# 5x4-soundboard_328p_TQFP.net
KiCad netlist of a schematic drawn in EAGLE
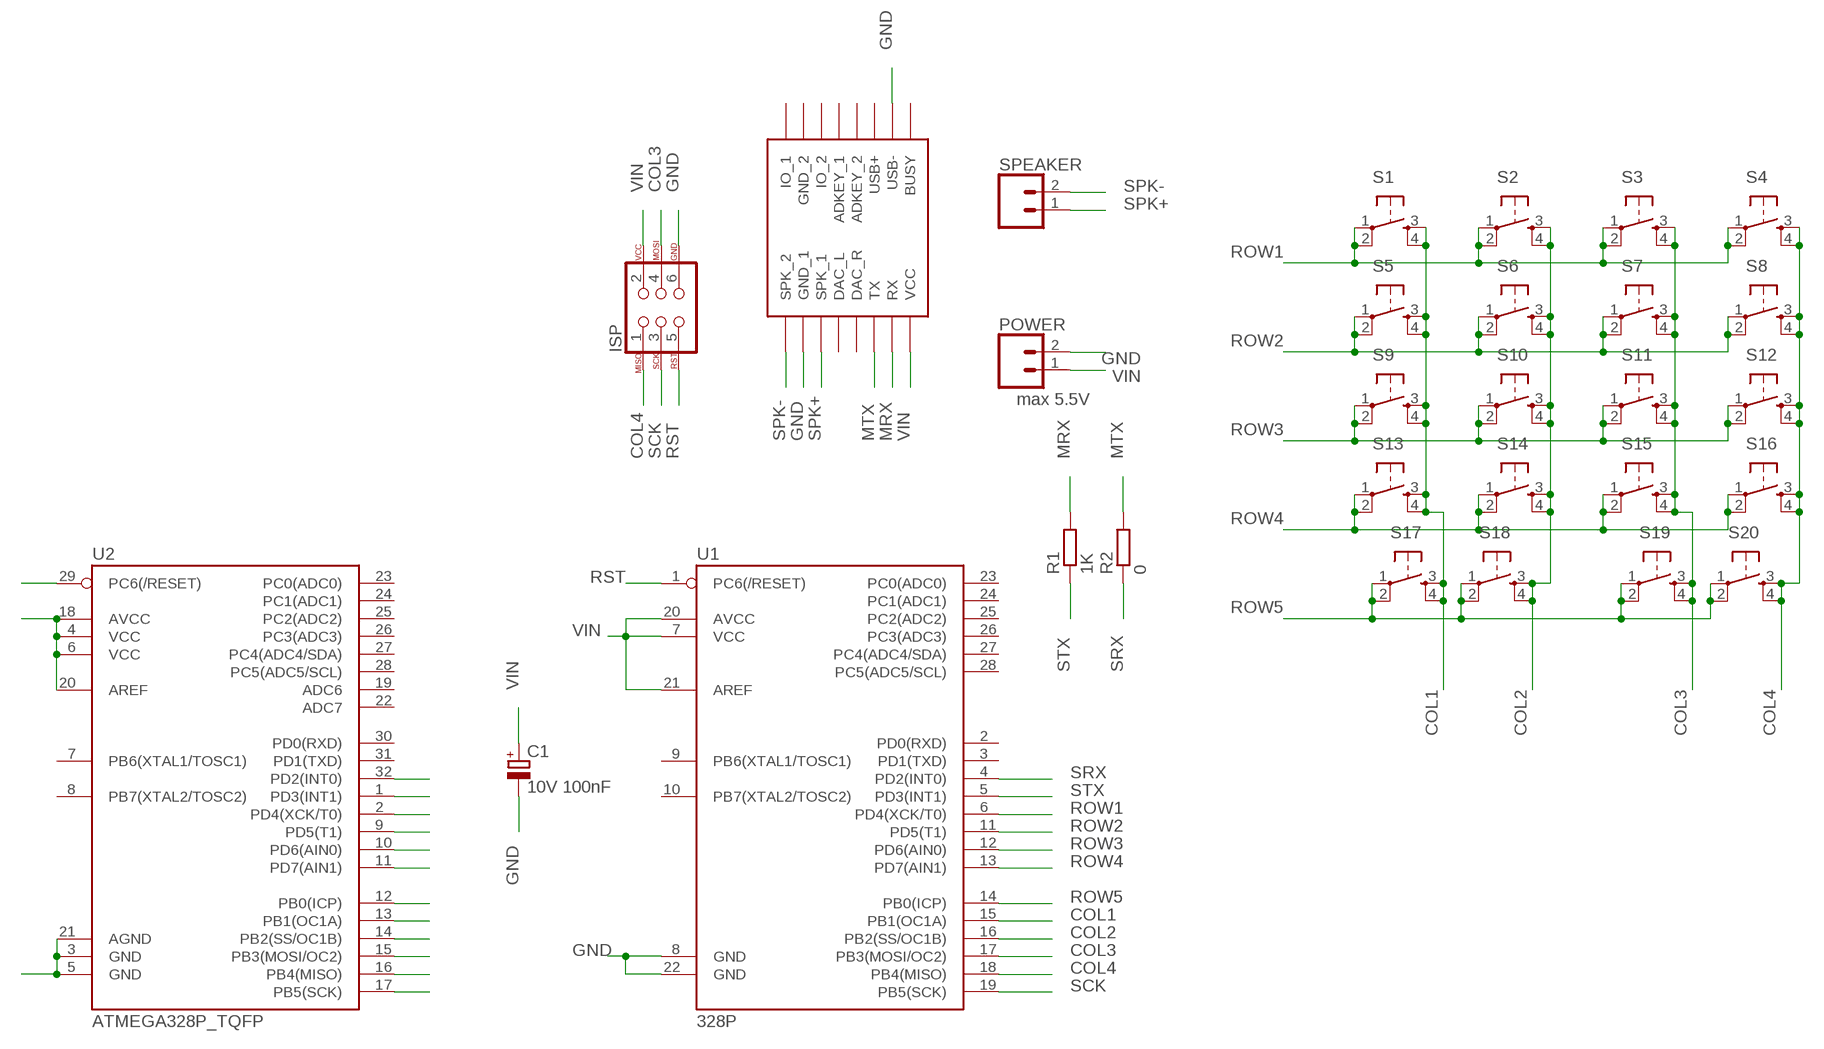
[diagram p0: schematic, sheet 1]

(export (version "E")
  (design (tool "Eeschema 10.0.6"))
  (components
    (comp (ref "C1")
      (value "10V 100nF")
      (footprint "eagle-import:E5-6")
      (libsource (lib "eagle-import") (part "CPOL-EUE5-6"))
    )
    (comp (ref "ISP")
      (value "AVR_SPI_PROG_3X2PTH")
      (footprint "eagle-import:2X3")
      (libsource (lib "eagle-import") (part "AVR_SPI_PROG_3X2PTH"))
    )
    (comp (ref "POWER")
      (value "CONN_02LOCK_LONGPADS")
      (footprint "eagle-import:1X02_LOCK_LONGPADS")
      (libsource (lib "eagle-import") (part "CONN_02LOCK_LONGPADS"))
    )
    (comp (ref "R1")
      (value "1K")
      (footprint "eagle-import:0207_10")
      (libsource (lib "eagle-import") (part "R-EU_0207/10"))
    )
    (comp (ref "R2")
      (value "0")
      (footprint "eagle-import:0207_10")
      (libsource (lib "eagle-import") (part "R-EU_0207/10"))
    )
    (comp (ref "S1")
      (value "TAC_SWITCHPTH")
      (footprint "eagle-import:TACTILE-PTH")
      (libsource (lib "eagle-import") (part "TAC_SWITCHPTH"))
    )
    (comp (ref "S2")
      (value "TAC_SWITCHPTH")
      (footprint "eagle-import:TACTILE-PTH")
      (libsource (lib "eagle-import") (part "TAC_SWITCHPTH"))
    )
    (comp (ref "S3")
      (value "TAC_SWITCHPTH")
      (footprint "eagle-import:TACTILE-PTH")
      (libsource (lib "eagle-import") (part "TAC_SWITCHPTH"))
    )
    (comp (ref "S4")
      (value "TAC_SWITCHPTH")
      (footprint "eagle-import:TACTILE-PTH")
      (libsource (lib "eagle-import") (part "TAC_SWITCHPTH"))
    )
    (comp (ref "S5")
      (value "TAC_SWITCHPTH")
      (footprint "eagle-import:TACTILE-PTH")
      (libsource (lib "eagle-import") (part "TAC_SWITCHPTH"))
    )
    (comp (ref "S6")
      (value "TAC_SWITCHPTH")
      (footprint "eagle-import:TACTILE-PTH")
      (libsource (lib "eagle-import") (part "TAC_SWITCHPTH"))
    )
    (comp (ref "S7")
      (value "TAC_SWITCHPTH")
      (footprint "eagle-import:TACTILE-PTH")
      (libsource (lib "eagle-import") (part "TAC_SWITCHPTH"))
    )
    (comp (ref "S8")
      (value "TAC_SWITCHPTH")
      (footprint "eagle-import:TACTILE-PTH")
      (libsource (lib "eagle-import") (part "TAC_SWITCHPTH"))
    )
    (comp (ref "S9")
      (value "TAC_SWITCHPTH")
      (footprint "eagle-import:TACTILE-PTH")
      (libsource (lib "eagle-import") (part "TAC_SWITCHPTH"))
    )
    (comp (ref "S10")
      (value "TAC_SWITCHPTH")
      (footprint "eagle-import:TACTILE-PTH")
      (libsource (lib "eagle-import") (part "TAC_SWITCHPTH"))
    )
    (comp (ref "S11")
      (value "TAC_SWITCHPTH")
      (footprint "eagle-import:TACTILE-PTH")
      (libsource (lib "eagle-import") (part "TAC_SWITCHPTH"))
    )
    (comp (ref "S12")
      (value "TAC_SWITCHPTH")
      (footprint "eagle-import:TACTILE-PTH")
      (libsource (lib "eagle-import") (part "TAC_SWITCHPTH"))
    )
    (comp (ref "S13")
      (value "TAC_SWITCHPTH")
      (footprint "eagle-import:TACTILE-PTH")
      (libsource (lib "eagle-import") (part "TAC_SWITCHPTH"))
    )
    (comp (ref "S14")
      (value "TAC_SWITCHPTH")
      (footprint "eagle-import:TACTILE-PTH")
      (libsource (lib "eagle-import") (part "TAC_SWITCHPTH"))
    )
    (comp (ref "S15")
      (value "TAC_SWITCHPTH")
      (footprint "eagle-import:TACTILE-PTH")
      (libsource (lib "eagle-import") (part "TAC_SWITCHPTH"))
    )
    (comp (ref "S16")
      (value "TAC_SWITCHPTH")
      (footprint "eagle-import:TACTILE-PTH")
      (libsource (lib "eagle-import") (part "TAC_SWITCHPTH"))
    )
    (comp (ref "S17")
      (value "TAC_SWITCHPTH")
      (footprint "eagle-import:TACTILE-PTH")
      (libsource (lib "eagle-import") (part "TAC_SWITCHPTH"))
    )
    (comp (ref "S18")
      (value "TAC_SWITCHPTH")
      (footprint "eagle-import:TACTILE-PTH")
      (libsource (lib "eagle-import") (part "TAC_SWITCHPTH"))
    )
    (comp (ref "S19")
      (value "TAC_SWITCHPTH")
      (footprint "eagle-import:TACTILE-PTH")
      (libsource (lib "eagle-import") (part "TAC_SWITCHPTH"))
    )
    (comp (ref "S20")
      (value "TAC_SWITCHPTH")
      (footprint "eagle-import:TACTILE-PTH")
      (libsource (lib "eagle-import") (part "TAC_SWITCHPTH"))
    )
    (comp (ref "SPEAKER")
      (value "CONN_02LOCK_LONGPADS")
      (footprint "eagle-import:1X02_LOCK_LONGPADS")
      (libsource (lib "eagle-import") (part "CONN_02LOCK_LONGPADS"))
    )
    (comp (ref "U$1")
      (value "DFPLAYER")
      (footprint "eagle-import:DFPLAYER")
      (libsource (lib "eagle-import") (part "DFPLAYER"))
    )
    (comp (ref "U1")
      (value "328P")
      (footprint "eagle-import:DIP28")
      (libsource (lib "eagle-import") (part "ATMEGA328P_PDIP"))
    )
    (comp (ref "U2")
      (value "ATMEGA328P_TQFP")
      (footprint "eagle-import:TQFP32-08")
      (libsource (lib "eagle-import") (part "ATMEGA328P_TQFP"))
    )
  )
  (nets
    (net (code "1") (name "/COL1") (class "Default")
      (node (ref "S1") (pin "3") (pinfunction "3_3") (pintype "passive"))
      (node (ref "S1") (pin "4") (pinfunction "4_4") (pintype "passive"))
      (node (ref "S13") (pin "3") (pinfunction "3_3") (pintype "passive"))
      (node (ref "S13") (pin "4") (pinfunction "4_4") (pintype "passive"))
      (node (ref "S17") (pin "3") (pinfunction "3_3") (pintype "passive"))
      (node (ref "S17") (pin "4") (pinfunction "4_4") (pintype "passive"))
      (node (ref "S5") (pin "3") (pinfunction "3_3") (pintype "passive"))
      (node (ref "S5") (pin "4") (pinfunction "4_4") (pintype "passive"))
      (node (ref "S9") (pin "3") (pinfunction "3_3") (pintype "passive"))
      (node (ref "S9") (pin "4") (pinfunction "4_4") (pintype "passive"))
      (node (ref "U1") (pin "15") (pinfunction "PB1(OC1A)_15") (pintype "bidirectional"))
      (node (ref "U2") (pin "13") (pinfunction "PB1(OC1A)_13") (pintype "bidirectional"))
    )
    (net (code "2") (name "/COL2") (class "Default")
      (node (ref "S10") (pin "3") (pinfunction "3_3") (pintype "passive"))
      (node (ref "S10") (pin "4") (pinfunction "4_4") (pintype "passive"))
      (node (ref "S14") (pin "3") (pinfunction "3_3") (pintype "passive"))
      (node (ref "S14") (pin "4") (pinfunction "4_4") (pintype "passive"))
      (node (ref "S18") (pin "3") (pinfunction "3_3") (pintype "passive"))
      (node (ref "S18") (pin "4") (pinfunction "4_4") (pintype "passive"))
      (node (ref "S2") (pin "3") (pinfunction "3_3") (pintype "passive"))
      (node (ref "S2") (pin "4") (pinfunction "4_4") (pintype "passive"))
      (node (ref "S6") (pin "3") (pinfunction "3_3") (pintype "passive"))
      (node (ref "S6") (pin "4") (pinfunction "4_4") (pintype "passive"))
      (node (ref "U1") (pin "16") (pinfunction "PB2(SS/OC1B)_16") (pintype "bidirectional"))
      (node (ref "U2") (pin "14") (pinfunction "PB2(SS/OC1B)_14") (pintype "bidirectional"))
    )
    (net (code "3") (name "/COL3") (class "Default")
      (node (ref "ISP") (pin "4") (pinfunction "4_4") (pintype "passive"))
      (node (ref "S11") (pin "3") (pinfunction "3_3") (pintype "passive"))
      (node (ref "S11") (pin "4") (pinfunction "4_4") (pintype "passive"))
      (node (ref "S15") (pin "3") (pinfunction "3_3") (pintype "passive"))
      (node (ref "S15") (pin "4") (pinfunction "4_4") (pintype "passive"))
      (node (ref "S19") (pin "3") (pinfunction "3_3") (pintype "passive"))
      (node (ref "S19") (pin "4") (pinfunction "4_4") (pintype "passive"))
      (node (ref "S3") (pin "3") (pinfunction "3_3") (pintype "passive"))
      (node (ref "S3") (pin "4") (pinfunction "4_4") (pintype "passive"))
      (node (ref "S7") (pin "3") (pinfunction "3_3") (pintype "passive"))
      (node (ref "S7") (pin "4") (pinfunction "4_4") (pintype "passive"))
      (node (ref "U1") (pin "17") (pinfunction "PB3(MOSI/OC2)_17") (pintype "bidirectional"))
      (node (ref "U2") (pin "15") (pinfunction "PB3(MOSI/OC2)_15") (pintype "bidirectional"))
    )
    (net (code "4") (name "/COL4") (class "Default")
      (node (ref "ISP") (pin "1") (pinfunction "1_1") (pintype "passive"))
      (node (ref "S12") (pin "3") (pinfunction "3_3") (pintype "passive"))
      (node (ref "S12") (pin "4") (pinfunction "4_4") (pintype "passive"))
      (node (ref "S16") (pin "3") (pinfunction "3_3") (pintype "passive"))
      (node (ref "S16") (pin "4") (pinfunction "4_4") (pintype "passive"))
      (node (ref "S20") (pin "3") (pinfunction "3_3") (pintype "passive"))
      (node (ref "S20") (pin "4") (pinfunction "4_4") (pintype "passive"))
      (node (ref "S4") (pin "3") (pinfunction "3_3") (pintype "passive"))
      (node (ref "S4") (pin "4") (pinfunction "4_4") (pintype "passive"))
      (node (ref "S8") (pin "3") (pinfunction "3_3") (pintype "passive"))
      (node (ref "S8") (pin "4") (pinfunction "4_4") (pintype "passive"))
      (node (ref "U1") (pin "18") (pinfunction "PB4(MISO)_18") (pintype "bidirectional"))
      (node (ref "U2") (pin "16") (pinfunction "PB4(MISO)_16") (pintype "bidirectional"))
    )
    (net (code "5") (name "/GND") (class "Default")
      (node (ref "C1") (pin "-") (pinfunction "-_-") (pintype "passive"))
      (node (ref "ISP") (pin "6") (pinfunction "6_6") (pintype "passive"))
      (node (ref "POWER") (pin "2") (pinfunction "2_2") (pintype "passive"))
      (node (ref "U$1") (pin "GND_1") (pinfunction "GND_1_GND_1") (pintype "bidirectional"))
      (node (ref "U$1") (pin "USB-") (pinfunction "USB-_USB-") (pintype "bidirectional"))
      (node (ref "U1") (pin "22") (pinfunction "GND_22") (pintype "bidirectional"))
      (node (ref "U1") (pin "8") (pinfunction "GND_8") (pintype "bidirectional"))
      (node (ref "U2") (pin "21") (pinfunction "AGND_21") (pintype "bidirectional"))
      (node (ref "U2") (pin "3") (pinfunction "GND_3") (pintype "bidirectional"))
      (node (ref "U2") (pin "5") (pinfunction "GND_5") (pintype "bidirectional"))
    )
    (net (code "6") (name "/MRX") (class "Default")
      (node (ref "R1") (pin "2") (pinfunction "2_2") (pintype "passive"))
      (node (ref "U$1") (pin "RX") (pinfunction "RX_RX") (pintype "bidirectional"))
    )
    (net (code "7") (name "/MTX") (class "Default")
      (node (ref "R2") (pin "2") (pinfunction "2_2") (pintype "passive"))
      (node (ref "U$1") (pin "TX") (pinfunction "TX_TX") (pintype "bidirectional"))
    )
    (net (code "8") (name "/ROW1") (class "Default")
      (node (ref "S1") (pin "1") (pinfunction "1_1") (pintype "passive"))
      (node (ref "S1") (pin "2") (pinfunction "2_2") (pintype "passive"))
      (node (ref "S2") (pin "1") (pinfunction "1_1") (pintype "passive"))
      (node (ref "S2") (pin "2") (pinfunction "2_2") (pintype "passive"))
      (node (ref "S3") (pin "1") (pinfunction "1_1") (pintype "passive"))
      (node (ref "S3") (pin "2") (pinfunction "2_2") (pintype "passive"))
      (node (ref "S4") (pin "1") (pinfunction "1_1") (pintype "passive"))
      (node (ref "S4") (pin "2") (pinfunction "2_2") (pintype "passive"))
      (node (ref "U1") (pin "6") (pinfunction "PD4(XCK/T0)_6") (pintype "bidirectional"))
      (node (ref "U2") (pin "2") (pinfunction "PD4(XCK/T0)_2") (pintype "bidirectional"))
    )
    (net (code "9") (name "/ROW2") (class "Default")
      (node (ref "S5") (pin "1") (pinfunction "1_1") (pintype "passive"))
      (node (ref "S5") (pin "2") (pinfunction "2_2") (pintype "passive"))
      (node (ref "S6") (pin "1") (pinfunction "1_1") (pintype "passive"))
      (node (ref "S6") (pin "2") (pinfunction "2_2") (pintype "passive"))
      (node (ref "S7") (pin "1") (pinfunction "1_1") (pintype "passive"))
      (node (ref "S7") (pin "2") (pinfunction "2_2") (pintype "passive"))
      (node (ref "S8") (pin "1") (pinfunction "1_1") (pintype "passive"))
      (node (ref "S8") (pin "2") (pinfunction "2_2") (pintype "passive"))
      (node (ref "U1") (pin "11") (pinfunction "PD5(T1)_11") (pintype "bidirectional"))
      (node (ref "U2") (pin "9") (pinfunction "PD5(T1)_9") (pintype "bidirectional"))
    )
    (net (code "10") (name "/ROW3") (class "Default")
      (node (ref "S10") (pin "1") (pinfunction "1_1") (pintype "passive"))
      (node (ref "S10") (pin "2") (pinfunction "2_2") (pintype "passive"))
      (node (ref "S11") (pin "1") (pinfunction "1_1") (pintype "passive"))
      (node (ref "S11") (pin "2") (pinfunction "2_2") (pintype "passive"))
      (node (ref "S12") (pin "1") (pinfunction "1_1") (pintype "passive"))
      (node (ref "S12") (pin "2") (pinfunction "2_2") (pintype "passive"))
      (node (ref "S9") (pin "1") (pinfunction "1_1") (pintype "passive"))
      (node (ref "S9") (pin "2") (pinfunction "2_2") (pintype "passive"))
      (node (ref "U1") (pin "12") (pinfunction "PD6(AIN0)_12") (pintype "bidirectional"))
      (node (ref "U2") (pin "10") (pinfunction "PD6(AIN0)_10") (pintype "bidirectional"))
    )
    (net (code "11") (name "/ROW4") (class "Default")
      (node (ref "S13") (pin "1") (pinfunction "1_1") (pintype "passive"))
      (node (ref "S13") (pin "2") (pinfunction "2_2") (pintype "passive"))
      (node (ref "S14") (pin "1") (pinfunction "1_1") (pintype "passive"))
      (node (ref "S14") (pin "2") (pinfunction "2_2") (pintype "passive"))
      (node (ref "S15") (pin "1") (pinfunction "1_1") (pintype "passive"))
      (node (ref "S15") (pin "2") (pinfunction "2_2") (pintype "passive"))
      (node (ref "S16") (pin "1") (pinfunction "1_1") (pintype "passive"))
      (node (ref "S16") (pin "2") (pinfunction "2_2") (pintype "passive"))
      (node (ref "U1") (pin "13") (pinfunction "PD7(AIN1)_13") (pintype "bidirectional"))
      (node (ref "U2") (pin "11") (pinfunction "PD7(AIN1)_11") (pintype "bidirectional"))
    )
    (net (code "12") (name "/ROW5") (class "Default")
      (node (ref "S17") (pin "1") (pinfunction "1_1") (pintype "passive"))
      (node (ref "S17") (pin "2") (pinfunction "2_2") (pintype "passive"))
      (node (ref "S18") (pin "1") (pinfunction "1_1") (pintype "passive"))
      (node (ref "S18") (pin "2") (pinfunction "2_2") (pintype "passive"))
      (node (ref "S19") (pin "1") (pinfunction "1_1") (pintype "passive"))
      (node (ref "S19") (pin "2") (pinfunction "2_2") (pintype "passive"))
      (node (ref "S20") (pin "1") (pinfunction "1_1") (pintype "passive"))
      (node (ref "S20") (pin "2") (pinfunction "2_2") (pintype "passive"))
      (node (ref "U1") (pin "14") (pinfunction "PB0(ICP)_14") (pintype "bidirectional"))
      (node (ref "U2") (pin "12") (pinfunction "PB0(ICP)_12") (pintype "bidirectional"))
    )
    (net (code "13") (name "/RST") (class "Default")
      (node (ref "ISP") (pin "5") (pinfunction "5_5") (pintype "passive"))
      (node (ref "U1") (pin "1") (pinfunction "PC6(/RESET)_1") (pintype "bidirectional"))
      (node (ref "U2") (pin "29") (pinfunction "PC6(/RESET)_29") (pintype "bidirectional"))
    )
    (net (code "14") (name "/SCK") (class "Default")
      (node (ref "ISP") (pin "3") (pinfunction "3_3") (pintype "passive"))
      (node (ref "U1") (pin "19") (pinfunction "PB5(SCK)_19") (pintype "bidirectional"))
      (node (ref "U2") (pin "17") (pinfunction "PB5(SCK)_17") (pintype "bidirectional"))
    )
    (net (code "15") (name "/SPK+") (class "Default")
      (node (ref "SPEAKER") (pin "1") (pinfunction "1_1") (pintype "passive"))
      (node (ref "U$1") (pin "SPK1") (pinfunction "SPK_1_SPK1") (pintype "bidirectional"))
    )
    (net (code "16") (name "/SPK-") (class "Default")
      (node (ref "SPEAKER") (pin "2") (pinfunction "2_2") (pintype "passive"))
      (node (ref "U$1") (pin "SPK2") (pinfunction "SPK_2_SPK2") (pintype "bidirectional"))
    )
    (net (code "17") (name "/SRX") (class "Default")
      (node (ref "R2") (pin "1") (pinfunction "1_1") (pintype "passive"))
      (node (ref "U1") (pin "4") (pinfunction "PD2(INT0)_4") (pintype "bidirectional"))
      (node (ref "U2") (pin "32") (pinfunction "PD2(INT0)_32") (pintype "bidirectional"))
    )
    (net (code "18") (name "/STX") (class "Default")
      (node (ref "R1") (pin "1") (pinfunction "1_1") (pintype "passive"))
      (node (ref "U1") (pin "5") (pinfunction "PD3(INT1)_5") (pintype "bidirectional"))
      (node (ref "U2") (pin "1") (pinfunction "PD3(INT1)_1") (pintype "bidirectional"))
    )
    (net (code "19") (name "/VIN") (class "Default")
      (node (ref "C1") (pin "+") (pinfunction "+_+") (pintype "passive"))
      (node (ref "ISP") (pin "2") (pinfunction "2_2") (pintype "passive"))
      (node (ref "POWER") (pin "1") (pinfunction "1_1") (pintype "passive"))
      (node (ref "U$1") (pin "VCC") (pinfunction "VCC_VCC") (pintype "bidirectional"))
      (node (ref "U1") (pin "20") (pinfunction "AVCC_20") (pintype "bidirectional"))
      (node (ref "U1") (pin "21") (pinfunction "AREF_21") (pintype "bidirectional"))
      (node (ref "U1") (pin "7") (pinfunction "VCC_7") (pintype "bidirectional"))
      (node (ref "U2") (pin "18") (pinfunction "AVCC_18") (pintype "bidirectional"))
      (node (ref "U2") (pin "20") (pinfunction "AREF_20") (pintype "bidirectional"))
      (node (ref "U2") (pin "4") (pinfunction "VCC_4") (pintype "bidirectional"))
      (node (ref "U2") (pin "6") (pinfunction "VCC_6") (pintype "bidirectional"))
    )
    (net (code "20") (name "unconnected-(U$1-ADKEY_1-PadADKEY1)") (class "Default")
      (node (ref "U$1") (pin "ADKEY1") (pinfunction "ADKEY_1_ADKEY1") (pintype "bidirectional"))
    )
    (net (code "21") (name "unconnected-(U$1-ADKEY_2-PadADKEY2)") (class "Default")
      (node (ref "U$1") (pin "ADKEY2") (pinfunction "ADKEY_2_ADKEY2") (pintype "bidirectional"))
    )
    (net (code "22") (name "unconnected-(U$1-IO_1-PadIO1)") (class "Default")
      (node (ref "U$1") (pin "IO1") (pinfunction "IO_1_IO1") (pintype "bidirectional"))
    )
    (net (code "23") (name "unconnected-(U$1-IO_2-PadIO2)") (class "Default")
      (node (ref "U$1") (pin "IO2") (pinfunction "IO_2_IO2") (pintype "bidirectional"))
    )
    (net (code "24") (name "unconnected-(U$1-PadBUSY)") (class "Default")
      (node (ref "U$1") (pin "BUSY") (pinfunction "BUSY_BUSY") (pintype "bidirectional"))
    )
    (net (code "25") (name "unconnected-(U$1-PadDAC_L)") (class "Default")
      (node (ref "U$1") (pin "DAC_L") (pinfunction "DAC_L_DAC_L") (pintype "bidirectional"))
    )
    (net (code "26") (name "unconnected-(U$1-PadDAC_R)") (class "Default")
      (node (ref "U$1") (pin "DAC_R") (pinfunction "DAC_R_DAC_R") (pintype "bidirectional"))
    )
    (net (code "27") (name "unconnected-(U$1-PadGND_2)") (class "Default")
      (node (ref "U$1") (pin "GND_2") (pinfunction "GND_2_GND_2") (pintype "bidirectional"))
    )
    (net (code "28") (name "unconnected-(U$1-PadUSB+)") (class "Default")
      (node (ref "U$1") (pin "USB+") (pinfunction "USB+_USB+") (pintype "bidirectional"))
    )
    (net (code "29") (name "unconnected-(U1-PB6(XTAL1{slash}TOSC1)-Pad9)") (class "Default")
      (node (ref "U1") (pin "9") (pinfunction "PB6(XTAL1/TOSC1)_9") (pintype "bidirectional"))
    )
    (net (code "30") (name "unconnected-(U1-PB7(XTAL2{slash}TOSC2)-Pad10)") (class "Default")
      (node (ref "U1") (pin "10") (pinfunction "PB7(XTAL2/TOSC2)_10") (pintype "bidirectional"))
    )
    (net (code "31") (name "unconnected-(U1-PC0(ADC0)-Pad23)") (class "Default")
      (node (ref "U1") (pin "23") (pinfunction "PC0(ADC0)_23") (pintype "bidirectional"))
    )
    (net (code "32") (name "unconnected-(U1-PC1(ADC1)-Pad24)") (class "Default")
      (node (ref "U1") (pin "24") (pinfunction "PC1(ADC1)_24") (pintype "bidirectional"))
    )
    (net (code "33") (name "unconnected-(U1-PC2(ADC2)-Pad25)") (class "Default")
      (node (ref "U1") (pin "25") (pinfunction "PC2(ADC2)_25") (pintype "bidirectional"))
    )
    (net (code "34") (name "unconnected-(U1-PC3(ADC3)-Pad26)") (class "Default")
      (node (ref "U1") (pin "26") (pinfunction "PC3(ADC3)_26") (pintype "bidirectional"))
    )
    (net (code "35") (name "unconnected-(U1-PC4(ADC4{slash}SDA)-Pad27)") (class "Default")
      (node (ref "U1") (pin "27") (pinfunction "PC4(ADC4/SDA)_27") (pintype "bidirectional"))
    )
    (net (code "36") (name "unconnected-(U1-PC5(ADC5{slash}SCL)-Pad28)") (class "Default")
      (node (ref "U1") (pin "28") (pinfunction "PC5(ADC5/SCL)_28") (pintype "bidirectional"))
    )
    (net (code "37") (name "unconnected-(U1-PD0(RXD)-Pad2)") (class "Default")
      (node (ref "U1") (pin "2") (pinfunction "PD0(RXD)_2") (pintype "bidirectional"))
    )
    (net (code "38") (name "unconnected-(U1-PD1(TXD)-Pad3)") (class "Default")
      (node (ref "U1") (pin "3") (pinfunction "PD1(TXD)_3") (pintype "bidirectional"))
    )
    (net (code "39") (name "unconnected-(U2-ADC6-Pad19)") (class "Default")
      (node (ref "U2") (pin "19") (pinfunction "ADC6_19") (pintype "bidirectional"))
    )
    (net (code "40") (name "unconnected-(U2-ADC7-Pad22)") (class "Default")
      (node (ref "U2") (pin "22") (pinfunction "ADC7_22") (pintype "bidirectional"))
    )
    (net (code "41") (name "unconnected-(U2-PB6(XTAL1{slash}TOSC1)-Pad7)") (class "Default")
      (node (ref "U2") (pin "7") (pinfunction "PB6(XTAL1/TOSC1)_7") (pintype "bidirectional"))
    )
    (net (code "42") (name "unconnected-(U2-PB7(XTAL2{slash}TOSC2)-Pad8)") (class "Default")
      (node (ref "U2") (pin "8") (pinfunction "PB7(XTAL2/TOSC2)_8") (pintype "bidirectional"))
    )
    (net (code "43") (name "unconnected-(U2-PC0(ADC0)-Pad23)") (class "Default")
      (node (ref "U2") (pin "23") (pinfunction "PC0(ADC0)_23") (pintype "bidirectional"))
    )
    (net (code "44") (name "unconnected-(U2-PC1(ADC1)-Pad24)") (class "Default")
      (node (ref "U2") (pin "24") (pinfunction "PC1(ADC1)_24") (pintype "bidirectional"))
    )
    (net (code "45") (name "unconnected-(U2-PC2(ADC2)-Pad25)") (class "Default")
      (node (ref "U2") (pin "25") (pinfunction "PC2(ADC2)_25") (pintype "bidirectional"))
    )
    (net (code "46") (name "unconnected-(U2-PC3(ADC3)-Pad26)") (class "Default")
      (node (ref "U2") (pin "26") (pinfunction "PC3(ADC3)_26") (pintype "bidirectional"))
    )
    (net (code "47") (name "unconnected-(U2-PC4(ADC4{slash}SDA)-Pad27)") (class "Default")
      (node (ref "U2") (pin "27") (pinfunction "PC4(ADC4/SDA)_27") (pintype "bidirectional"))
    )
    (net (code "48") (name "unconnected-(U2-PC5(ADC5{slash}SCL)-Pad28)") (class "Default")
      (node (ref "U2") (pin "28") (pinfunction "PC5(ADC5/SCL)_28") (pintype "bidirectional"))
    )
    (net (code "49") (name "unconnected-(U2-PD0(RXD)-Pad30)") (class "Default")
      (node (ref "U2") (pin "30") (pinfunction "PD0(RXD)_30") (pintype "bidirectional"))
    )
    (net (code "50") (name "unconnected-(U2-PD1(TXD)-Pad31)") (class "Default")
      (node (ref "U2") (pin "31") (pinfunction "PD1(TXD)_31") (pintype "bidirectional"))
    )
  )
)
